# avoccado-avr-pcb-felina-icsp.net
KiCad netlist of a schematic drawn in EAGLE
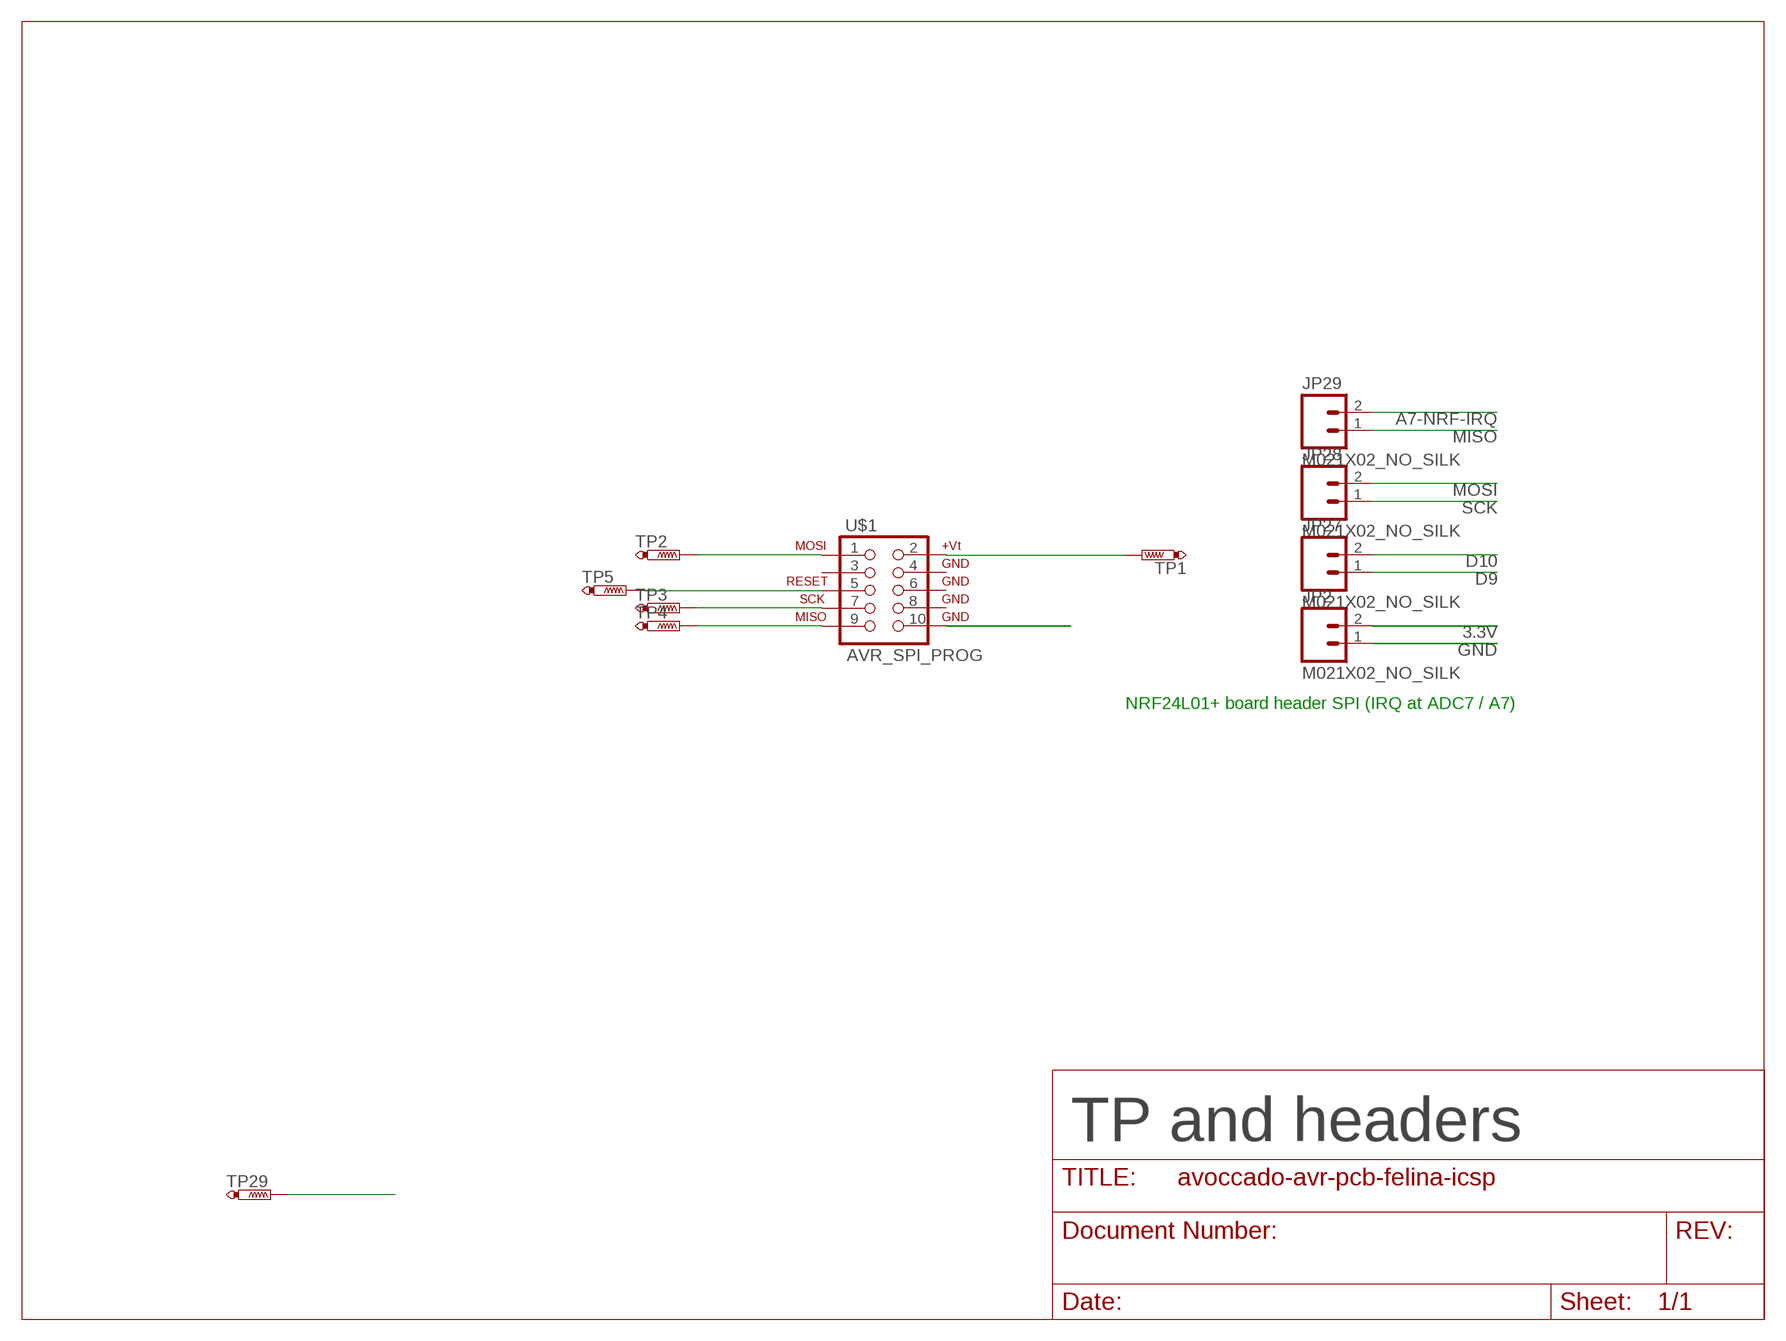
[diagram p0: schematic, sheet 1, part 1 of 2]
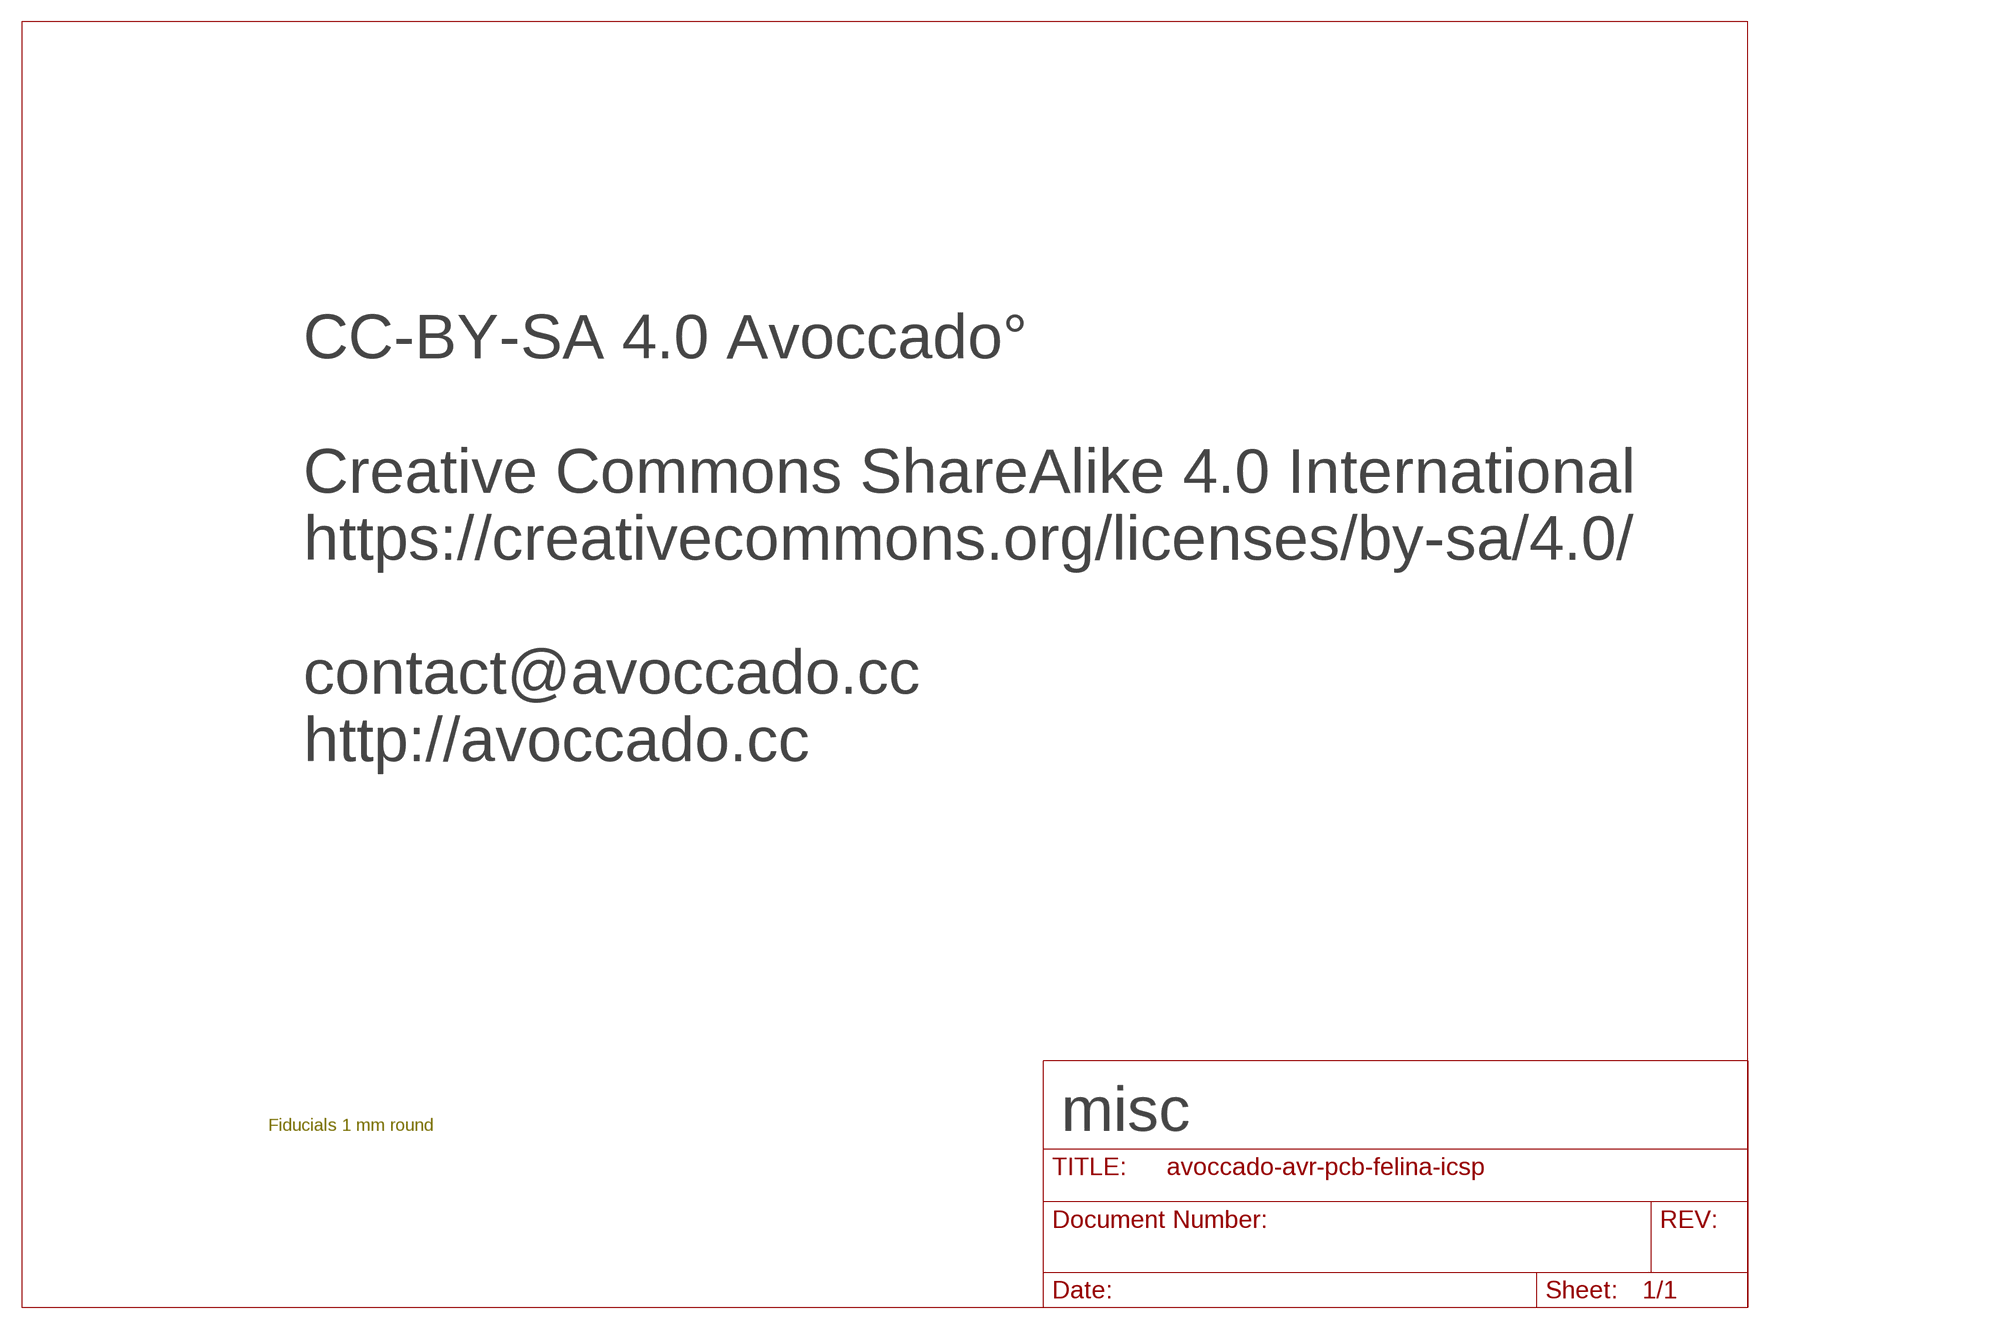
[diagram p1: schematic, sheet 1, part 2 of 2]

(export (version "E")
  (design (tool "Eeschema 10.0.6"))
  (components
    (comp (ref "JP2")
      (value "M021X02_NO_SILK")
      (footprint "eagle-import:1X02_NO_SILK")
      (libsource (lib "eagle-import") (part "M021X02_NO_SILK"))
    )
    (comp (ref "JP27")
      (value "M021X02_NO_SILK")
      (footprint "eagle-import:1X02_NO_SILK")
      (libsource (lib "eagle-import") (part "M021X02_NO_SILK"))
    )
    (comp (ref "JP28")
      (value "M021X02_NO_SILK")
      (footprint "eagle-import:1X02_NO_SILK")
      (libsource (lib "eagle-import") (part "M021X02_NO_SILK"))
    )
    (comp (ref "JP29")
      (value "M021X02_NO_SILK")
      (footprint "eagle-import:1X02_NO_SILK")
      (libsource (lib "eagle-import") (part "M021X02_NO_SILK"))
    )
    (comp (ref "TP1")
      (value "PTR1PAD1-13")
      (footprint "eagle-import:P1-13")
      (libsource (lib "eagle-import") (part "PTR1PAD1-13"))
    )
    (comp (ref "TP2")
      (value "PTR1PAD1-13")
      (footprint "eagle-import:P1-13")
      (libsource (lib "eagle-import") (part "PTR1PAD1-13"))
    )
    (comp (ref "TP3")
      (value "PTR1PAD1-13")
      (footprint "eagle-import:P1-13")
      (libsource (lib "eagle-import") (part "PTR1PAD1-13"))
    )
    (comp (ref "TP4")
      (value "PTR1PAD1-13")
      (footprint "eagle-import:P1-13")
      (libsource (lib "eagle-import") (part "PTR1PAD1-13"))
    )
    (comp (ref "TP5")
      (value "PTR1PAD1-13")
      (footprint "eagle-import:P1-13")
      (libsource (lib "eagle-import") (part "PTR1PAD1-13"))
    )
    (comp (ref "TP29")
      (value "PTR1PAD1-13")
      (footprint "eagle-import:P1-13")
      (libsource (lib "eagle-import") (part "PTR1PAD1-13"))
    )
    (comp (ref "U$1")
      (value "AVR_SPI_PROG")
      (footprint "eagle-import:AVR_ICSP")
      (libsource (lib "eagle-import") (part "AVR_SPI_PROG"))
    )
  )
  (nets
    (net (code "1") (name "/3.3V") (class "Default")
      (node (ref "JP2") (pin "2") (pinfunction "2_2") (pintype "passive"))
      (node (ref "TP1") (pin "TP") (pinfunction "TP_TP") (pintype "input"))
      (node (ref "U$1") (pin "2") (pinfunction "2_2") (pintype "passive"))
    )
    (net (code "2") (name "/A7-NRF-IRQ") (class "Default")
      (node (ref "JP29") (pin "2") (pinfunction "2_2") (pintype "passive"))
    )
    (net (code "3") (name "/D9") (class "Default")
      (node (ref "JP27") (pin "1") (pinfunction "1_1") (pintype "passive"))
    )
    (net (code "4") (name "/D10") (class "Default")
      (node (ref "JP27") (pin "2") (pinfunction "2_2") (pintype "passive"))
    )
    (net (code "5") (name "/GND") (class "Default")
      (node (ref "JP2") (pin "1") (pinfunction "1_1") (pintype "passive"))
      (node (ref "TP29") (pin "TP") (pinfunction "TP_TP") (pintype "input"))
      (node (ref "U$1") (pin "10") (pinfunction "10_10") (pintype "passive"))
    )
    (net (code "6") (name "/MISO") (class "Default")
      (node (ref "JP29") (pin "1") (pinfunction "1_1") (pintype "passive"))
      (node (ref "TP4") (pin "TP") (pinfunction "TP_TP") (pintype "input"))
      (node (ref "U$1") (pin "9") (pinfunction "9_9") (pintype "passive"))
    )
    (net (code "7") (name "/MOSI") (class "Default")
      (node (ref "JP28") (pin "2") (pinfunction "2_2") (pintype "passive"))
      (node (ref "TP2") (pin "TP") (pinfunction "TP_TP") (pintype "input"))
      (node (ref "U$1") (pin "1") (pinfunction "1_1") (pintype "passive"))
    )
    (net (code "8") (name "/SCK") (class "Default")
      (node (ref "JP28") (pin "1") (pinfunction "1_1") (pintype "passive"))
      (node (ref "TP3") (pin "TP") (pinfunction "TP_TP") (pintype "input"))
      (node (ref "U$1") (pin "7") (pinfunction "7_7") (pintype "passive"))
    )
    (net (code "9") (name "Net-(TP5-PadTP)") (class "Default")
      (node (ref "TP5") (pin "TP") (pinfunction "TP_TP") (pintype "input"))
      (node (ref "U$1") (pin "5") (pinfunction "5_5") (pintype "passive"))
    )
    (net (code "10") (name "unconnected-(U$1-Pad3)") (class "Default")
      (node (ref "U$1") (pin "3") (pinfunction "3_3") (pintype "passive"))
    )
    (net (code "11") (name "unconnected-(U$1-Pad4)") (class "Default")
      (node (ref "U$1") (pin "4") (pinfunction "4_4") (pintype "passive"))
    )
    (net (code "12") (name "unconnected-(U$1-Pad6)") (class "Default")
      (node (ref "U$1") (pin "6") (pinfunction "6_6") (pintype "passive"))
    )
    (net (code "13") (name "unconnected-(U$1-Pad8)") (class "Default")
      (node (ref "U$1") (pin "8") (pinfunction "8_8") (pintype "passive"))
    )
  )
)
